# PowerManagment_V2.net
KiCad netlist of a schematic drawn in Altium Designer
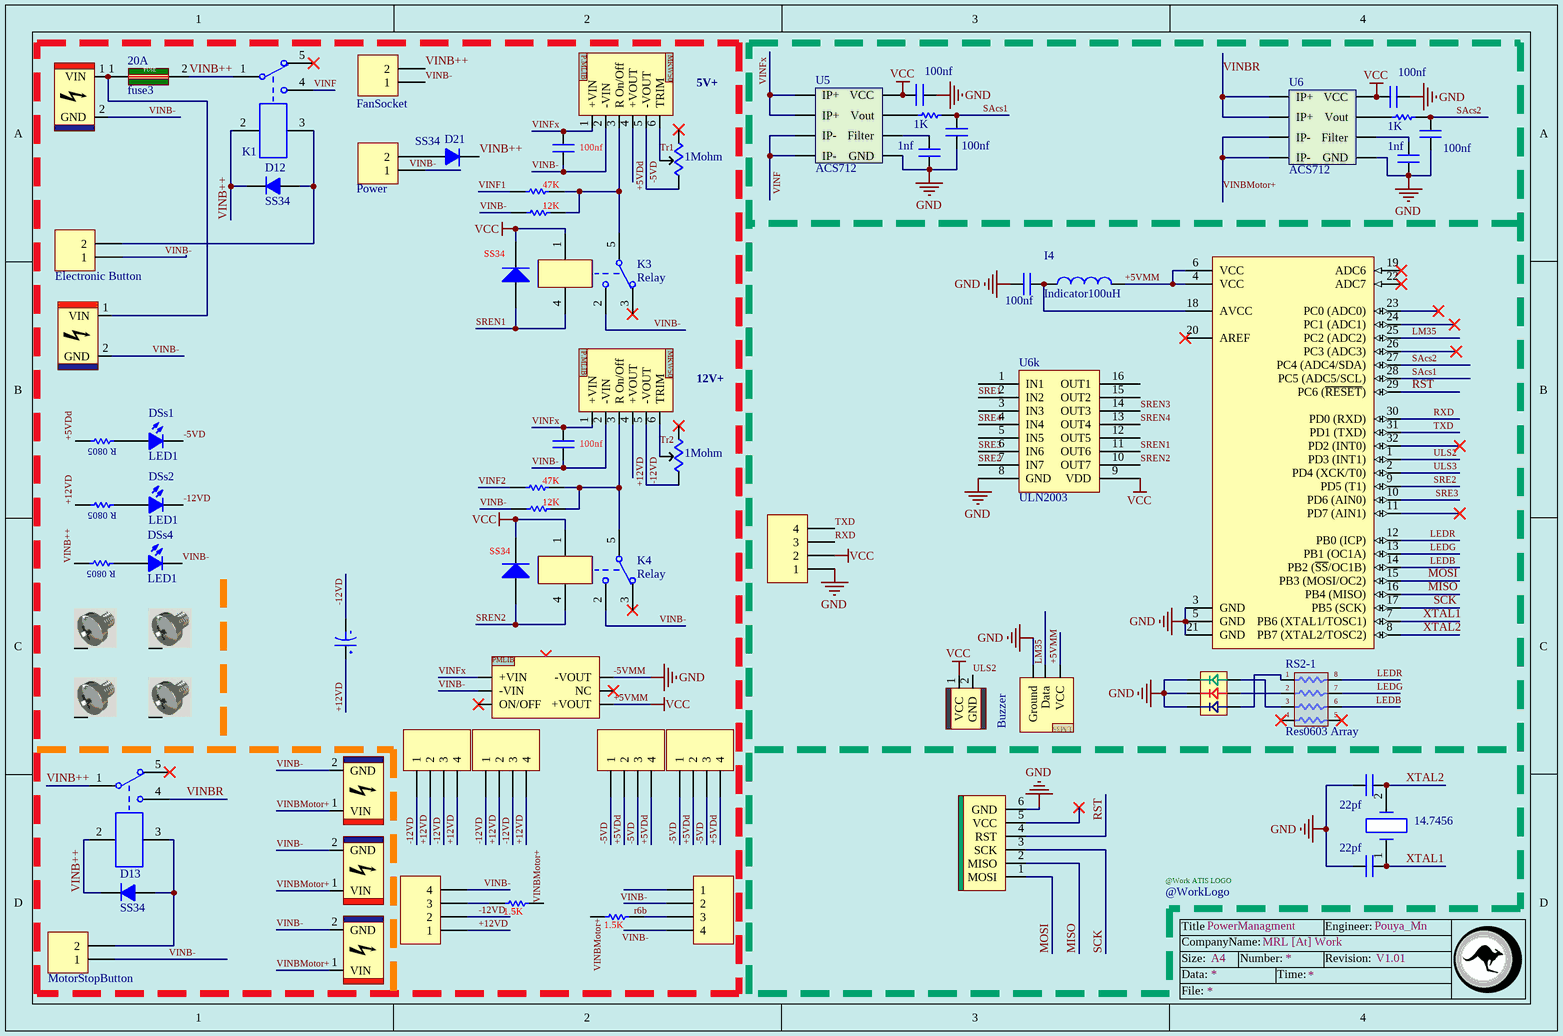
[diagram p0: PowerManagment_V2.SchDoc]

(export (version "E")
  (design (tool "Eeschema 10.0.6"))
  (components
    (comp (ref "1SA") (value "Screw") (footprint "Screw") (libsource (lib "PMLIB") (part "Screw")))
    (comp (ref "2SA") (value "Screw") (footprint "Screw") (libsource (lib "PMLIB") (part "Screw")))
    (comp (ref "3SA") (value "Screw") (footprint "Screw") (libsource (lib "PMLIB") (part "Screw")))
    (comp (ref "4SA") (value "Screw") (footprint "Screw") (libsource (lib "PMLIB") (part "Screw")))
    (comp (ref "20A") (value "fuse3") (footprint "fuse 5*20") (libsource (lib "PMLIB") (part "fuse3")))
    (comp (ref "ATX1") (value "FanSocket") (footprint "ATX_1.2S") (libsource (lib "PMLIB") (part "ATX_1.2R")))
    (comp (ref "ATX3")
      (value "MotorStopButton")
      (footprint "ATX_1.2S")
      (libsource (lib "PMLIB") (part "ATX_1.2R"))
    )
    (comp (ref "ATX4")
      (value "Electronic Button")
      (footprint "ATX_1.2S")
      (libsource (lib "PMLIB") (part "ATX_1.2R"))
    )
    (comp (ref "ATX6") (value "Power") (footprint "ATX_1.2S") (libsource (lib "PMLIB") (part "ATX_1.2R")))
    (comp (ref "ATXX1") (value "ATX2*2R") (footprint "ATX2*2S") (libsource (lib "PMLIB") (part "ATX2*2R")))
    (comp (ref "ATXX2") (value "ATX2*2R") (footprint "ATX2*2S") (libsource (lib "PMLIB") (part "ATX2*2R")))
    (comp (ref "ATXX6") (value "ATX2*2R") (footprint "ATX2*2S") (libsource (lib "PMLIB") (part "ATX2*2R")))
    (comp (ref "ATXX9") (value "ATX2*2R") (footprint "ATX2*2S") (libsource (lib "PMLIB") (part "ATX2*2R")))
    (comp (ref "B2") (value "Buzzer") (footprint "Buzzer") (libsource (lib "PMLIB") (part "Buzzer")))
    (comp (ref "C2")
      (value "100nF")
      (footprint "Cap0805")
      (description "surface mount capacitor (size 805)")
      (libsource (lib "PMLIB") (part "Cap0805"))
    )
    (comp (ref "C11")
      (value "100nf")
      (footprint "Cap0805")
      (description "surface mount capacitor (size 805)")
      (libsource (lib "PMLIB") (part "Cap0805"))
    )
    (comp (ref "C22")
      (value "100nF")
      (footprint "Cap0805")
      (description "surface mount capacitor (size 805)")
      (libsource (lib "PMLIB") (part "Cap0805"))
    )
    (comp (ref "C28")
      (value "22pf")
      (footprint "Cap0805")
      (description "surface mount capacitor (size 805)")
      (libsource (lib "PMLIB") (part "Cap0805"))
    )
    (comp (ref "C29")
      (value "22pf")
      (footprint "Cap0805")
      (description "surface mount capacitor (size 805)")
      (libsource (lib "PMLIB") (part "Cap0805"))
    )
    (comp (ref "CA1")
      (value "100nf")
      (footprint "Cap0805")
      (description "surface mount capacitor (size 805)")
      (libsource (lib "PMLIB") (part "Cap0805"))
    )
    (comp (ref "CA2")
      (value "1nf")
      (footprint "Cap0805")
      (description "surface mount capacitor (size 805)")
      (libsource (lib "PMLIB") (part "Cap0805"))
    )
    (comp (ref "CA3")
      (value "1nf")
      (footprint "Cap0805")
      (description "surface mount capacitor (size 805)")
      (libsource (lib "PMLIB") (part "Cap0805"))
    )
    (comp (ref "CA4")
      (value "100nf")
      (footprint "Cap0805")
      (description "surface mount capacitor (size 805)")
      (libsource (lib "PMLIB") (part "Cap0805"))
    )
    (comp (ref "CA6")
      (value "100nf")
      (footprint "Cap0805")
      (description "surface mount capacitor (size 805)")
      (libsource (lib "PMLIB") (part "Cap0805"))
    )
    (comp (ref "CA7")
      (value "100nf")
      (footprint "Cap0805")
      (description "surface mount capacitor (size 805)")
      (libsource (lib "PMLIB") (part "Cap0805"))
    )
    (comp (ref "Cr3") (value "4.7Uf") (footprint "Cap_4mm") (libsource (lib "PMLIB") (part "Cap_Pola")))
    (comp (ref "D12") (value "SS34") (footprint "Diod-1A-SMD") (libsource (lib "") (part "Diode_1")))
    (comp (ref "D13") (value "SS34") (footprint "Diod-1A-SMD") (libsource (lib "") (part "Diode_1")))
    (comp (ref "D21") (value "SS34") (footprint "Diod-3A-SMD") (libsource (lib "") (part "Diode_1")))
    (comp (ref "DE1") (value "SS34") (footprint "Diod-1A-SMD") (libsource (lib "PMLIB") (part "Diode")))
    (comp (ref "DE2") (value "SS34") (footprint "Diod-1A-SMD") (libsource (lib "PMLIB") (part "Diode")))
    (comp (ref "DSs1") (value "LED1") (footprint "Led0805") (libsource (lib "PMLIB") (part "LED1")))
    (comp (ref "DSs2") (value "LED1") (footprint "Led0805") (libsource (lib "PMLIB") (part "LED1")))
    (comp (ref "DSs4") (value "LED1") (footprint "Led0805") (libsource (lib "PMLIB") (part "LED1")))
    (comp (ref "f") (value "MINMAXMEW") (footprint "MINMAXMEW") (libsource (lib "PMLIB") (part "MINMAXMEW")))
    (comp (ref "I4")
      (value "Indicator100uH")
      (footprint "1206")
      (libsource (lib "PMLIB") (part "Indicator100uH"))
    )
    (comp (ref "K1") (value "Relay_7") (footprint "Relay_7") (libsource (lib "PMLIB") (part "Relay_7")))
    (comp (ref "K3")
      (value "Relay")
      (footprint "RelayMinionSmall")
      (libsource (lib "PMLIB") (part "RelayMilon"))
    )
    (comp (ref "K4")
      (value "Relay")
      (footprint "RelayMinionSmall")
      (libsource (lib "PMLIB") (part "RelayMilon"))
    )
    (comp (ref "K5") (value "Relay_7") (footprint "Relay_7") (libsource (lib "PMLIB") (part "Relay_7")))
    (comp (ref "lm") (value "Lm35") (footprint "UGN3503") (libsource (lib "PMLIB") (part "Lm35")))
    (comp (ref "Logo")
      (value "@WorkLogo")
      (footprint "@WorkATISLogo")
      (libsource (lib "PMLIB") (part "@WorkLogo"))
    )
    (comp (ref "M1") (value "5V+") (footprint "MK50") (libsource (lib "PMLIB") (part "MK50_DCTODC")))
    (comp (ref "M2") (value "12V+") (footprint "MK50") (libsource (lib "PMLIB") (part "MK50_DCTODC")))
    (comp (ref "Pro1")
      (value "Programmer")
      (footprint "Programmer")
      (libsource (lib "PMLIB") (part "Programmer"))
    )
    (comp (ref "R46") (value "Res 0805") (footprint "R0805") (libsource (lib "PMLIB") (part "Res 0805")))
    (comp (ref "R47") (value "Res 0805") (footprint "R0805") (libsource (lib "PMLIB") (part "Res 0805")))
    (comp (ref "R49") (value "Res 0805") (footprint "R0805") (libsource (lib "PMLIB") (part "Res 0805")))
    (comp (ref "RA1") (value "1K") (footprint "R0805") (libsource (lib "PMLIB") (part "Res 0805")))
    (comp (ref "RA2-2") (value "1K") (footprint "R0805") (libsource (lib "PMLIB") (part "Res 0805")))
    (comp (ref "RGB") (value "RGBSMD") (footprint "LEDRGBSMD") (libsource (lib "PMLIB") (part "RGBSMD")))
    (comp (ref "RS1") (value "47K") (footprint "R0805") (libsource (lib "PMLIB") (part "Res 0805")))
    (comp (ref "RS1r") (value "1.5K") (footprint "R0805") (libsource (lib "PMLIB") (part "Res 0805")))
    (comp (ref "RS1rd") (value "1.5K") (footprint "R0805") (libsource (lib "PMLIB") (part "Res 0805")))
    (comp (ref "RS2") (value "12K") (footprint "R0805") (libsource (lib "PMLIB") (part "Res 0805")))
    (comp (ref "RS2-1")
      (value "Res0603 Array")
      (footprint "Res 0603 Array")
      (libsource (lib "PMLIB") (part "Res0603 Array"))
    )
    (comp (ref "RS3") (value "47K") (footprint "R0805") (libsource (lib "PMLIB") (part "Res 0805")))
    (comp (ref "RS4") (value "12K") (footprint "R0805") (libsource (lib "PMLIB") (part "Res 0805")))
    (comp (ref "Rt1") (value "1Mohm") (footprint "Multi_tern") (libsource (lib "PMLIB") (part "POT1")))
    (comp (ref "Rt2") (value "1Mohm") (footprint "Multi_tern") (libsource (lib "PMLIB") (part "POT1")))
    (comp (ref "spox1")
      (value "SPOX1*4")
      (footprint "SPOX_1*4RIGHT")
      (libsource (lib "PMLIB") (part "SPOX1*4"))
    )
    (comp (ref "spox2") (value "SPOX1*4") (footprint "SPOX_1*4RIGHT") (libsource (lib "") (part "SPOX1*4_1")))
    (comp (ref "spox12")
      (value "SPOX1*4")
      (footprint "SPOX_1*4RIGHT")
      (libsource (lib "PMLIB") (part "SPOX1*4"))
    )
    (comp (ref "T1")
      (value "Connector T")
      (footprint "SocketS06")
      (libsource (lib "PMLIB") (part "Connector T"))
    )
    (comp (ref "TR1")
      (value "Connector T")
      (footprint "T_Connector")
      (libsource (lib "") (part "Connector T_1"))
    )
    (comp (ref "TR2")
      (value "Connector T")
      (footprint "T_Connector")
      (libsource (lib "") (part "Connector T_1"))
    )
    (comp (ref "TR3")
      (value "Connector T")
      (footprint "T_Connector")
      (libsource (lib "") (part "Connector T_1"))
    )
    (comp (ref "TR5")
      (value "Connector T")
      (footprint "T_Connector")
      (libsource (lib "PMLIB") (part "Connector T"))
    )
    (comp (ref "U4")
      (value "ATmega8-16AU")
      (footprint "32A_N")
      (libsource (lib "Atmel Microcontroller megaAVR") (part "ATmega8-16AU"))
    )
    (comp (ref "U5")
      (value "ACS712")
      (footprint "SOP8")
      (description "Hall effect Current Sensor")
      (libsource (lib "PMLIB") (part "ACS712"))
    )
    (comp (ref "U6")
      (value "ACS712")
      (footprint "SOP8")
      (description "Hall effect Current Sensor")
      (libsource (lib "PMLIB") (part "ACS712"))
    )
    (comp (ref "U6k") (value "ULN2003") (footprint "SO16") (libsource (lib "PMLIB") (part "ULN2003")))
    (comp (ref "Y") (value "14.7456") (footprint "CrystallB") (libsource (lib "PMLIB") (part "Xtal 1")))
  )
  (nets
    (net (code "1") (name "/+5VDd") (class "Default")
      (node (ref "ATXX1") (pin "2") (pinfunction "2_2") (pintype "passive"))
      (node (ref "ATXX1") (pin "4") (pinfunction "4_4") (pintype "passive"))
      (node (ref "ATXX6") (pin "2") (pinfunction "2_2") (pintype "passive"))
      (node (ref "ATXX6") (pin "4") (pinfunction "4_4") (pintype "passive"))
      (node (ref "M1") (pin "4") (pinfunction "+VOUT_4") (pintype "passive"))
      (node (ref "R47") (pin "1") (pinfunction "1_1") (pintype "passive"))
    )
    (net (code "2") (name "/+12VD") (class "Default")
      (node (ref "ATXX2") (pin "2") (pinfunction "2_2") (pintype "passive"))
      (node (ref "ATXX2") (pin "4") (pinfunction "4_4") (pintype "passive"))
      (node (ref "ATXX9") (pin "2") (pinfunction "2_2") (pintype "passive"))
      (node (ref "ATXX9") (pin "4") (pinfunction "4_4") (pintype "passive"))
      (node (ref "Cr3") (pin "2") (pinfunction "2_2") (pintype "passive"))
      (node (ref "M2") (pin "4") (pinfunction "+VOUT_4") (pintype "passive"))
      (node (ref "R46") (pin "1") (pinfunction "1_1") (pintype "passive"))
      (node (ref "spox1") (pin "1") (pinfunction "1_1") (pintype "passive"))
    )
    (net (code "3") (name "/-5VD") (class "Default")
      (node (ref "ATXX1") (pin "1") (pinfunction "1_1") (pintype "passive"))
      (node (ref "ATXX1") (pin "3") (pinfunction "3_3") (pintype "passive"))
      (node (ref "ATXX6") (pin "1") (pinfunction "1_1") (pintype "passive"))
      (node (ref "ATXX6") (pin "3") (pinfunction "3_3") (pintype "passive"))
      (node (ref "DSs1") (pin "K") (pinfunction "K_K") (pintype "passive"))
      (node (ref "M1") (pin "5") (pinfunction "-VOUT_5") (pintype "passive"))
      (node (ref "Rt1") (pin "1") (pinfunction "1_1") (pintype "passive"))
    )
    (net (code "4") (name "/-12VD") (class "Default")
      (node (ref "ATXX2") (pin "1") (pinfunction "1_1") (pintype "passive"))
      (node (ref "ATXX2") (pin "3") (pinfunction "3_3") (pintype "passive"))
      (node (ref "ATXX9") (pin "1") (pinfunction "1_1") (pintype "passive"))
      (node (ref "ATXX9") (pin "3") (pinfunction "3_3") (pintype "passive"))
      (node (ref "Cr3") (pin "1") (pinfunction "1_1") (pintype "passive"))
      (node (ref "DSs2") (pin "K") (pinfunction "K_K") (pintype "passive"))
      (node (ref "M2") (pin "5") (pinfunction "-VOUT_5") (pintype "passive"))
      (node (ref "Rt2") (pin "1") (pinfunction "1_1") (pintype "passive"))
      (node (ref "spox1") (pin "2") (pinfunction "2_2") (pintype "passive"))
    )
    (net (code "5") (name "/LEDB") (class "Default")
      (node (ref "RS2-1") (pin "6") (pinfunction "6_6") (pintype "passive"))
      (node (ref "U4") (pin "14") (pinfunction "PB2_(~{SS}/OC1B)_14") (pintype "bidirectional"))
    )
    (net (code "6") (name "/LEDG") (class "Default")
      (node (ref "RS2-1") (pin "7") (pinfunction "7_7") (pintype "passive"))
      (node (ref "U4") (pin "13") (pinfunction "PB1_(OC1A)_13") (pintype "bidirectional"))
    )
    (net (code "7") (name "/LEDR") (class "Default")
      (node (ref "RS2-1") (pin "8") (pinfunction "8_8") (pintype "passive"))
      (node (ref "U4") (pin "12") (pinfunction "PB0_(ICP)_12") (pintype "bidirectional"))
    )
    (net (code "8") (name "/LM35") (class "Default")
      (node (ref "U4") (pin "25") (pinfunction "PC2_(ADC2)_25") (pintype "bidirectional"))
      (node (ref "lm") (pin "2") (pinfunction "Data_2") (pintype "passive"))
    )
    (net (code "9") (name "/MISO") (class "Default")
      (node (ref "Pro1") (pin "2") (pinfunction "MISO_2") (pintype "passive"))
      (node (ref "U4") (pin "16") (pinfunction "PB4_(MISO)_16") (pintype "bidirectional"))
    )
    (net (code "10") (name "/MOSI") (class "Default")
      (node (ref "Pro1") (pin "1") (pinfunction "MOSI_1") (pintype "passive"))
      (node (ref "U4") (pin "15") (pinfunction "PB3_(MOSI/OC2)_15") (pintype "bidirectional"))
    )
    (net (code "11") (name "/RST") (class "Default")
      (node (ref "Pro1") (pin "4") (pinfunction "RST_4") (pintype "passive"))
      (node (ref "U4") (pin "29") (pinfunction "PC6_(~{RESET})_29") (pintype "bidirectional"))
    )
    (net (code "12") (name "/RXD") (class "Default")
      (node (ref "U4") (pin "30") (pinfunction "PD0_(RXD)_30") (pintype "bidirectional"))
      (node (ref "spox12") (pin "3") (pinfunction "3_3") (pintype "passive"))
    )
    (net (code "13") (name "/SAcs1") (class "Default")
      (node (ref "CA6") (pin "2") (pinfunction "2_2") (pintype "passive"))
      (node (ref "RA1") (pin "1") (pinfunction "1_1") (pintype "passive"))
      (node (ref "U4") (pin "28") (pinfunction "PC5_(ADC5/SCL)_28") (pintype "bidirectional"))
    )
    (net (code "14") (name "/SAcs2") (class "Default")
      (node (ref "CA7") (pin "2") (pinfunction "2_2") (pintype "passive"))
      (node (ref "RA2-2") (pin "1") (pinfunction "1_1") (pintype "passive"))
      (node (ref "U4") (pin "27") (pinfunction "PC4_(ADC4/SDA)_27") (pintype "bidirectional"))
    )
    (net (code "15") (name "/SCK") (class "Default")
      (node (ref "Pro1") (pin "3") (pinfunction "SCK_3") (pintype "passive"))
      (node (ref "U4") (pin "17") (pinfunction "PB5_(SCK)_17") (pintype "bidirectional"))
    )
    (net (code "16") (name "/SRE1") (class "Default")
      (node (ref "U6k") (pin "2") (pinfunction "IN2_2") (pintype "passive"))
    )
    (net (code "17") (name "/SRE2") (class "Default")
      (node (ref "U4") (pin "9") (pinfunction "PD5_(T1)_9") (pintype "bidirectional"))
      (node (ref "U6k") (pin "7") (pinfunction "IN7_7") (pintype "passive"))
    )
    (net (code "18") (name "/SRE3") (class "Default")
      (node (ref "U4") (pin "10") (pinfunction "PD6_(AIN0)_10") (pintype "bidirectional"))
      (node (ref "U6k") (pin "6") (pinfunction "IN6_6") (pintype "passive"))
    )
    (net (code "19") (name "/SRE4") (class "Default")
      (node (ref "U6k") (pin "4") (pinfunction "IN4_4") (pintype "passive"))
    )
    (net (code "20") (name "/SREN1") (class "Default")
      (node (ref "DE1") (pin "A") (pinfunction "A_A") (pintype "passive"))
      (node (ref "K3") (pin "4") (pinfunction "4_4") (pintype "passive"))
      (node (ref "U6k") (pin "11") (pinfunction "OUT6_11") (pintype "passive"))
    )
    (net (code "21") (name "/SREN2") (class "Default")
      (node (ref "DE2") (pin "A") (pinfunction "A_A") (pintype "passive"))
      (node (ref "K4") (pin "4") (pinfunction "4_4") (pintype "passive"))
      (node (ref "U6k") (pin "10") (pinfunction "OUT7_10") (pintype "passive"))
    )
    (net (code "22") (name "/SREN3") (class "Default")
      (node (ref "U6k") (pin "14") (pinfunction "OUT3_14") (pintype "passive"))
    )
    (net (code "23") (name "/SREN4") (class "Default")
      (node (ref "U6k") (pin "13") (pinfunction "OUT4_13") (pintype "passive"))
    )
    (net (code "24") (name "/TXD") (class "Default")
      (node (ref "U4") (pin "31") (pinfunction "PD1_(TXD)_31") (pintype "bidirectional"))
      (node (ref "spox12") (pin "4") (pinfunction "4_4") (pintype "passive"))
    )
    (net (code "25") (name "/Tr1") (class "Default")
      (node (ref "M1") (pin "6") (pinfunction "TRIM_6") (pintype "passive"))
      (node (ref "Rt1") (pin "2") (pinfunction "2_2") (pintype "passive"))
    )
    (net (code "26") (name "/Tr2") (class "Default")
      (node (ref "M2") (pin "6") (pinfunction "TRIM_6") (pintype "passive"))
      (node (ref "Rt2") (pin "2") (pinfunction "2_2") (pintype "passive"))
    )
    (net (code "27") (name "/ULS2") (class "Default")
      (node (ref "B2") (pin "2") (pinfunction "GND_2") (pintype "passive"))
      (node (ref "U4") (pin "1") (pinfunction "PD3_(INT1)_1") (pintype "bidirectional"))
    )
    (net (code "28") (name "/ULS3") (class "Default")
      (node (ref "U4") (pin "2") (pinfunction "PD4_(XCK/T0)_2") (pintype "bidirectional"))
    )
    (net (code "29") (name "/VINB++") (class "Default")
      (node (ref "20A") (pin "2") (pinfunction "OUT_2") (pintype "passive"))
      (node (ref "ATX6") (pin "2") (pinfunction "2_2") (pintype "passive"))
      (node (ref "D12") (pin "K") (pinfunction "K_K") (pintype "passive"))
      (node (ref "D13") (pin "K") (pinfunction "K_K") (pintype "passive"))
      (node (ref "D21") (pin "K") (pinfunction "K_K") (pintype "passive"))
      (node (ref "K1") (pin "1") (pinfunction "1_1") (pintype "passive"))
      (node (ref "K1") (pin "2") (pinfunction "2_2") (pintype "passive"))
      (node (ref "K5") (pin "1") (pinfunction "1_1") (pintype "passive"))
      (node (ref "K5") (pin "2") (pinfunction "2_2") (pintype "passive"))
      (node (ref "R49") (pin "1") (pinfunction "1_1") (pintype "passive"))
    )
    (net (code "30") (name "/VINB-") (class "Default")
      (node (ref "ATX3") (pin "1") (pinfunction "1_1") (pintype "passive"))
      (node (ref "ATX4") (pin "1") (pinfunction "1_1") (pintype "passive"))
      (node (ref "ATX6") (pin "1") (pinfunction "1_1") (pintype "passive"))
      (node (ref "C2") (pin "1") (pinfunction "1_1") (pintype "passive"))
      (node (ref "C22") (pin "1") (pinfunction "1_1") (pintype "passive"))
      (node (ref "DSs4") (pin "K") (pinfunction "K_K") (pintype "passive"))
      (node (ref "K3") (pin "2") (pinfunction "2_2") (pintype "passive"))
      (node (ref "K4") (pin "2") (pinfunction "2_2") (pintype "passive"))
      (node (ref "M1") (pin "2") (pinfunction "-VIN_2") (pintype "passive"))
      (node (ref "M2") (pin "2") (pinfunction "-VIN_2") (pintype "passive"))
      (node (ref "RS2") (pin "2") (pinfunction "2_2") (pintype "passive"))
      (node (ref "RS4") (pin "2") (pinfunction "2_2") (pintype "passive"))
      (node (ref "T1") (pin "2") (pinfunction "GND_2") (pintype "passive"))
      (node (ref "TR1") (pin "2") (pinfunction "GND_2") (pintype "passive"))
      (node (ref "TR2") (pin "2") (pinfunction "GND_2") (pintype "passive"))
      (node (ref "TR3") (pin "2") (pinfunction "GND_2") (pintype "passive"))
      (node (ref "TR5") (pin "2") (pinfunction "GND_2") (pintype "passive"))
      (node (ref "f") (pin "1") (pinfunction "-VIN_1") (pintype "passive"))
      (node (ref "spox1") (pin "4") (pinfunction "4_4") (pintype "passive"))
      (node (ref "spox2") (pin "1") (pinfunction "1_1") (pintype "passive"))
      (node (ref "spox2") (pin "4") (pinfunction "4_4") (pintype "passive"))
    )
    (net (code "31") (name "/VINBMotor+") (class "Default")
      (node (ref "RS1r") (pin "2") (pinfunction "2_2") (pintype "passive"))
      (node (ref "RS1rd") (pin "2") (pinfunction "2_2") (pintype "passive"))
      (node (ref "TR1") (pin "1") (pinfunction "VIN_1") (pintype "passive"))
      (node (ref "TR2") (pin "1") (pinfunction "VIN_1") (pintype "passive"))
      (node (ref "TR3") (pin "1") (pinfunction "VIN_1") (pintype "passive"))
      (node (ref "U6") (pin "3") (pinfunction "IP-_3") (pintype "passive"))
      (node (ref "U6") (pin "4") (pinfunction "IP-_4") (pintype "passive"))
    )
    (net (code "32") (name "/VINBR") (class "Default")
      (node (ref "K5") (pin "4") (pinfunction "4_4") (pintype "passive"))
      (node (ref "U6") (pin "1") (pinfunction "IP+_1") (pintype "passive"))
      (node (ref "U6") (pin "2") (pinfunction "IP+_2") (pintype "passive"))
    )
    (net (code "33") (name "/VINF") (class "Default")
      (node (ref "K1") (pin "4") (pinfunction "4_4") (pintype "passive"))
      (node (ref "U5") (pin "3") (pinfunction "IP-_3") (pintype "passive"))
      (node (ref "U5") (pin "4") (pinfunction "IP-_4") (pintype "passive"))
    )
    (net (code "34") (name "/VINF1") (class "Default")
      (node (ref "RS1") (pin "2") (pinfunction "2_2") (pintype "passive"))
    )
    (net (code "35") (name "/VINF2") (class "Default")
      (node (ref "RS3") (pin "2") (pinfunction "2_2") (pintype "passive"))
    )
    (net (code "36") (name "/VINFx") (class "Default")
      (node (ref "C2") (pin "2") (pinfunction "2_2") (pintype "passive"))
      (node (ref "C22") (pin "2") (pinfunction "2_2") (pintype "passive"))
      (node (ref "M1") (pin "1") (pinfunction "+VIN_1") (pintype "passive"))
      (node (ref "M2") (pin "1") (pinfunction "+VIN_1") (pintype "passive"))
      (node (ref "U5") (pin "1") (pinfunction "IP+_1") (pintype "passive"))
      (node (ref "U5") (pin "2") (pinfunction "IP+_2") (pintype "passive"))
      (node (ref "f") (pin "2") (pinfunction "+VIN_2") (pintype "passive"))
    )
    (net (code "37") (name "/XTAL1") (class "Default")
      (node (ref "C28") (pin "1") (pinfunction "1_1") (pintype "passive"))
      (node (ref "U4") (pin "7") (pinfunction "PB6_(XTAL1/TOSC1)_7") (pintype "bidirectional"))
      (node (ref "Y") (pin "1") (pinfunction "1_1") (pintype "passive"))
    )
    (net (code "38") (name "/XTAL2") (class "Default")
      (node (ref "C29") (pin "1") (pinfunction "1_1") (pintype "passive"))
      (node (ref "U4") (pin "8") (pinfunction "PB7_(XTAL2/TOSC2)_8") (pintype "bidirectional"))
      (node (ref "Y") (pin "2") (pinfunction "2_2") (pintype "passive"))
    )
    (net (code "39") (name "/r6b") (class "Default")
      (node (ref "spox2") (pin "2") (pinfunction "2_2") (pintype "passive"))
    )
    (net (code "40") (name "GND") (class "Default")
      (node (ref "C11") (pin "1") (pinfunction "1_1") (pintype "passive"))
      (node (ref "C28") (pin "2") (pinfunction "2_2") (pintype "passive"))
      (node (ref "C29") (pin "2") (pinfunction "2_2") (pintype "passive"))
      (node (ref "CA1") (pin "2") (pinfunction "2_2") (pintype "passive"))
      (node (ref "CA2") (pin "2") (pinfunction "2_2") (pintype "passive"))
      (node (ref "CA3") (pin "2") (pinfunction "2_2") (pintype "passive"))
      (node (ref "CA4") (pin "2") (pinfunction "2_2") (pintype "passive"))
      (node (ref "CA6") (pin "1") (pinfunction "1_1") (pintype "passive"))
      (node (ref "CA7") (pin "1") (pinfunction "1_1") (pintype "passive"))
      (node (ref "Pro1") (pin "6") (pinfunction "GND_6") (pintype "passive"))
      (node (ref "RGB") (pin "1") (pinfunction "1_1") (pintype "passive"))
      (node (ref "RGB") (pin "2") (pinfunction "2_2") (pintype "passive"))
      (node (ref "RGB") (pin "3") (pinfunction "3_3") (pintype "passive"))
      (node (ref "U4") (pin "21") (pinfunction "GND_21") (pintype "power_in"))
      (node (ref "U4") (pin "3") (pinfunction "GND_3") (pintype "power_in"))
      (node (ref "U4") (pin "5") (pinfunction "GND_5") (pintype "power_in"))
      (node (ref "U5") (pin "5") (pinfunction "GND_5") (pintype "passive"))
      (node (ref "U6") (pin "5") (pinfunction "GND_5") (pintype "passive"))
      (node (ref "U6k") (pin "8") (pinfunction "GND_8") (pintype "passive"))
      (node (ref "f") (pin "7") (pinfunction "-VOUT_7") (pintype "passive"))
      (node (ref "lm") (pin "3") (pinfunction "Ground_3") (pintype "passive"))
      (node (ref "spox12") (pin "1") (pinfunction "1_1") (pintype "passive"))
    )
    (net (code "41") (name "Net-(20A-IN)") (class "Default")
      (node (ref "20A") (pin "1") (pinfunction "IN_1") (pintype "passive"))
      (node (ref "T1") (pin "1") (pinfunction "VIN_1") (pintype "passive"))
      (node (ref "TR5") (pin "1") (pinfunction "VIN_1") (pintype "passive"))
    )
    (net (code "42") (name "Net-(ATX1-Pad2)") (class "Default")
      (node (ref "ATX1") (pin "2") (pinfunction "2_2") (pintype "passive"))
      (node (ref "D21") (pin "A") (pinfunction "A_A") (pintype "passive"))
    )
    (net (code "43") (name "Net-(ATX3-Pad2)") (class "Default")
      (node (ref "ATX3") (pin "2") (pinfunction "2_2") (pintype "passive"))
      (node (ref "D13") (pin "A") (pinfunction "A_A") (pintype "passive"))
      (node (ref "K5") (pin "3") (pinfunction "3_3") (pintype "passive"))
    )
    (net (code "44") (name "Net-(ATX4-Pad2)") (class "Default")
      (node (ref "ATX4") (pin "2") (pinfunction "2_2") (pintype "passive"))
      (node (ref "D12") (pin "A") (pinfunction "A_A") (pintype "passive"))
      (node (ref "K1") (pin "3") (pinfunction "3_3") (pintype "passive"))
    )
    (net (code "45") (name "Net-(DSs1-PadA)") (class "Default")
      (node (ref "DSs1") (pin "A") (pinfunction "A_A") (pintype "passive"))
      (node (ref "R47") (pin "2") (pinfunction "2_2") (pintype "passive"))
    )
    (net (code "46") (name "Net-(DSs2-PadA)") (class "Default")
      (node (ref "DSs2") (pin "A") (pinfunction "A_A") (pintype "passive"))
      (node (ref "R46") (pin "2") (pinfunction "2_2") (pintype "passive"))
    )
    (net (code "47") (name "Net-(DSs4-PadA)") (class "Default")
      (node (ref "DSs4") (pin "A") (pinfunction "A_A") (pintype "passive"))
      (node (ref "R49") (pin "2") (pinfunction "2_2") (pintype "passive"))
    )
    (net (code "48") (name "Net-(M1-R_On{slash}Off)") (class "Default")
      (node (ref "K3") (pin "5") (pinfunction "5_5") (pintype "passive"))
      (node (ref "M1") (pin "3") (pinfunction "R_On/Off_3") (pintype "passive"))
      (node (ref "RS1") (pin "1") (pinfunction "1_1") (pintype "passive"))
      (node (ref "RS2") (pin "1") (pinfunction "1_1") (pintype "passive"))
    )
    (net (code "49") (name "Net-(M2-R_On{slash}Off)") (class "Default")
      (node (ref "K4") (pin "5") (pinfunction "5_5") (pintype "passive"))
      (node (ref "M2") (pin "3") (pinfunction "R_On/Off_3") (pintype "passive"))
      (node (ref "RS3") (pin "1") (pinfunction "1_1") (pintype "passive"))
      (node (ref "RS4") (pin "1") (pinfunction "1_1") (pintype "passive"))
    )
    (net (code "50") (name "Net-(RGB-Pad4)") (class "Default")
      (node (ref "RGB") (pin "4") (pinfunction "4_4") (pintype "passive"))
      (node (ref "RS2-1") (pin "1") (pinfunction "1_1") (pintype "passive"))
    )
    (net (code "51") (name "Net-(RGB-Pad5)") (class "Default")
      (node (ref "RGB") (pin "5") (pinfunction "5_5") (pintype "passive"))
      (node (ref "RS2-1") (pin "2") (pinfunction "2_2") (pintype "passive"))
    )
    (net (code "52") (name "Net-(RGB-Pad6)") (class "Default")
      (node (ref "RGB") (pin "6") (pinfunction "6_6") (pintype "passive"))
      (node (ref "RS2-1") (pin "3") (pinfunction "3_3") (pintype "passive"))
    )
    (net (code "53") (name "Net-(RS1r-Pad1)") (class "Default")
      (node (ref "RS1r") (pin "1") (pinfunction "1_1") (pintype "passive"))
      (node (ref "spox1") (pin "3") (pinfunction "3_3") (pintype "passive"))
    )
    (net (code "54") (name "Net-(RS1rd-Pad1)") (class "Default")
      (node (ref "RS1rd") (pin "1") (pinfunction "1_1") (pintype "passive"))
      (node (ref "spox2") (pin "3") (pinfunction "3_3") (pintype "passive"))
    )
    (net (code "55") (name "Net-(U4-AVCC)") (class "Default")
      (node (ref "C11") (pin "2") (pinfunction "2_2") (pintype "passive"))
      (node (ref "I4") (pin "1") (pinfunction "1_1") (pintype "passive"))
      (node (ref "U4") (pin "18") (pinfunction "AVCC_18") (pintype "power_in"))
    )
    (net (code "56") (name "Net-(U5-Filter)") (class "Default")
      (node (ref "CA3") (pin "1") (pinfunction "1_1") (pintype "passive"))
      (node (ref "U5") (pin "6") (pinfunction "Filter_6") (pintype "passive"))
    )
    (net (code "57") (name "Net-(U5-Vout)") (class "Default")
      (node (ref "RA1") (pin "2") (pinfunction "2_2") (pintype "passive"))
      (node (ref "U5") (pin "7") (pinfunction "Vout_7") (pintype "passive"))
    )
    (net (code "58") (name "Net-(U6-Filter)") (class "Default")
      (node (ref "CA2") (pin "1") (pinfunction "1_1") (pintype "passive"))
      (node (ref "U6") (pin "6") (pinfunction "Filter_6") (pintype "passive"))
    )
    (net (code "59") (name "Net-(U6-Vout)") (class "Default")
      (node (ref "RA2-2") (pin "2") (pinfunction "2_2") (pintype "passive"))
      (node (ref "U6") (pin "7") (pinfunction "Vout_7") (pintype "passive"))
    )
    (net (code "60") (name "VCC") (class "Default")
      (node (ref "B2") (pin "1") (pinfunction "VCC_1") (pintype "passive"))
      (node (ref "CA1") (pin "1") (pinfunction "1_1") (pintype "passive"))
      (node (ref "CA4") (pin "1") (pinfunction "1_1") (pintype "passive"))
      (node (ref "DE1") (pin "K") (pinfunction "K_K") (pintype "passive"))
      (node (ref "DE2") (pin "K") (pinfunction "K_K") (pintype "passive"))
      (node (ref "I4") (pin "2") (pinfunction "2_2") (pintype "passive"))
      (node (ref "K3") (pin "1") (pinfunction "1_1") (pintype "passive"))
      (node (ref "K4") (pin "1") (pinfunction "1_1") (pintype "passive"))
      (node (ref "U4") (pin "4") (pinfunction "VCC_4") (pintype "power_in"))
      (node (ref "U4") (pin "6") (pinfunction "VCC_6") (pintype "power_in"))
      (node (ref "U5") (pin "8") (pinfunction "VCC_8") (pintype "passive"))
      (node (ref "U6") (pin "8") (pinfunction "VCC_8") (pintype "passive"))
      (node (ref "U6k") (pin "9") (pinfunction "VDD_9") (pintype "passive"))
      (node (ref "f") (pin "6") (pinfunction "+VOUT_6") (pintype "passive"))
      (node (ref "lm") (pin "1") (pinfunction "VCC_1") (pintype "passive"))
      (node (ref "spox12") (pin "2") (pinfunction "2_2") (pintype "passive"))
    )
    (net (code "61") (name "unconnected-(1SA-PadS)") (class "Default")
      (node (ref "1SA") (pin "S") (pinfunction "S_S") (pintype "passive"))
    )
    (net (code "62") (name "unconnected-(2SA-PadS)") (class "Default")
      (node (ref "2SA") (pin "S") (pinfunction "S_S") (pintype "passive"))
    )
    (net (code "63") (name "unconnected-(3SA-PadS)") (class "Default")
      (node (ref "3SA") (pin "S") (pinfunction "S_S") (pintype "passive"))
    )
    (net (code "64") (name "unconnected-(4SA-PadS)") (class "Default")
      (node (ref "4SA") (pin "S") (pinfunction "S_S") (pintype "passive"))
    )
    (net (code "65") (name "unconnected-(ATX1-Pad1)") (class "Default")
      (node (ref "ATX1") (pin "1") (pinfunction "1_1") (pintype "passive"))
    )
    (net (code "66") (name "unconnected-(K1-Pad5)") (class "Default")
      (node (ref "K1") (pin "5") (pinfunction "5_5") (pintype "passive+no_connect"))
    )
    (net (code "67") (name "unconnected-(K3-Pad3)") (class "Default")
      (node (ref "K3") (pin "3") (pinfunction "3_3") (pintype "passive+no_connect"))
    )
    (net (code "68") (name "unconnected-(K4-Pad3)") (class "Default")
      (node (ref "K4") (pin "3") (pinfunction "3_3") (pintype "passive+no_connect"))
    )
    (net (code "69") (name "unconnected-(K5-Pad5)") (class "Default")
      (node (ref "K5") (pin "5") (pinfunction "5_5") (pintype "passive+no_connect"))
    )
    (net (code "70") (name "unconnected-(Pro1-VCC-Pad5)") (class "Default")
      (node (ref "Pro1") (pin "5") (pinfunction "VCC_5") (pintype "passive+no_connect"))
    )
    (net (code "71") (name "unconnected-(RS2-1-Pad4)") (class "Default")
      (node (ref "RS2-1") (pin "4") (pinfunction "4_4") (pintype "passive+no_connect"))
    )
    (net (code "72") (name "unconnected-(RS2-1-Pad5)") (class "Default")
      (node (ref "RS2-1") (pin "5") (pinfunction "5_5") (pintype "passive+no_connect"))
    )
    (net (code "73") (name "unconnected-(Rt1-Pad3)") (class "Default")
      (node (ref "Rt1") (pin "3") (pinfunction "3_3") (pintype "passive+no_connect"))
    )
    (net (code "74") (name "unconnected-(Rt2-Pad3)") (class "Default")
      (node (ref "Rt2") (pin "3") (pinfunction "3_3") (pintype "passive+no_connect"))
    )
    (net (code "75") (name "unconnected-(U4-ADC6-Pad19)") (class "Default")
      (node (ref "U4") (pin "19") (pinfunction "ADC6_19") (pintype "input+no_connect"))
    )
    (net (code "76") (name "unconnected-(U4-ADC7-Pad22)") (class "Default")
      (node (ref "U4") (pin "22") (pinfunction "ADC7_22") (pintype "input+no_connect"))
    )
    (net (code "77") (name "unconnected-(U4-AREF-Pad20)") (class "Default")
      (node (ref "U4") (pin "20") (pinfunction "AREF_20") (pintype "passive+no_connect"))
    )
    (net (code "78") (name "unconnected-(U4-PC0_(ADC0)-Pad23)") (class "Default")
      (node (ref "U4") (pin "23") (pinfunction "PC0_(ADC0)_23") (pintype "bidirectional+no_connect"))
    )
    (net (code "79") (name "unconnected-(U4-PC1_(ADC1)-Pad24)") (class "Default")
      (node (ref "U4") (pin "24") (pinfunction "PC1_(ADC1)_24") (pintype "bidirectional+no_connect"))
    )
    (net (code "80") (name "unconnected-(U4-PC3_(ADC3)-Pad26)") (class "Default")
      (node (ref "U4") (pin "26") (pinfunction "PC3_(ADC3)_26") (pintype "bidirectional+no_connect"))
    )
    (net (code "81") (name "unconnected-(U4-PD2_(INT0)-Pad32)") (class "Default")
      (node (ref "U4") (pin "32") (pinfunction "PD2_(INT0)_32") (pintype "bidirectional+no_connect"))
    )
    (net (code "82") (name "unconnected-(U4-PD7_(AIN1)-Pad11)") (class "Default")
      (node (ref "U4") (pin "11") (pinfunction "PD7_(AIN1)_11") (pintype "bidirectional+no_connect"))
    )
    (net (code "83") (name "unconnected-(U6k-IN1-Pad1)") (class "Default")
      (node (ref "U6k") (pin "1") (pinfunction "IN1_1") (pintype "passive"))
    )
    (net (code "84") (name "unconnected-(U6k-IN3-Pad3)") (class "Default")
      (node (ref "U6k") (pin "3") (pinfunction "IN3_3") (pintype "passive"))
    )
    (net (code "85") (name "unconnected-(U6k-IN5-Pad5)") (class "Default")
      (node (ref "U6k") (pin "5") (pinfunction "IN5_5") (pintype "passive"))
    )
    (net (code "86") (name "unconnected-(U6k-OUT1-Pad16)") (class "Default")
      (node (ref "U6k") (pin "16") (pinfunction "OUT1_16") (pintype "passive"))
    )
    (net (code "87") (name "unconnected-(U6k-OUT2-Pad15)") (class "Default")
      (node (ref "U6k") (pin "15") (pinfunction "OUT2_15") (pintype "passive"))
    )
    (net (code "88") (name "unconnected-(U6k-OUT5-Pad12)") (class "Default")
      (node (ref "U6k") (pin "12") (pinfunction "OUT5_12") (pintype "passive"))
    )
    (net (code "89") (name "unconnected-(f-NC-Pad5)") (class "Default")
      (node (ref "f") (pin "5") (pinfunction "NC_5") (pintype "passive+no_connect"))
    )
    (net (code "90") (name "unconnected-(f-NC-Pad8)") (class "Default")
      (node (ref "f") (pin "8") (pinfunction "NC_8") (pintype "passive+no_connect"))
    )
    (net (code "91") (name "unconnected-(f-ON{slash}OFF-Pad3)") (class "Default")
      (node (ref "f") (pin "3") (pinfunction "ON/OFF_3") (pintype "passive+no_connect"))
    )
  )
)
